# AIRDCR.net
KiCad netlist of a schematic drawn in EAGLE
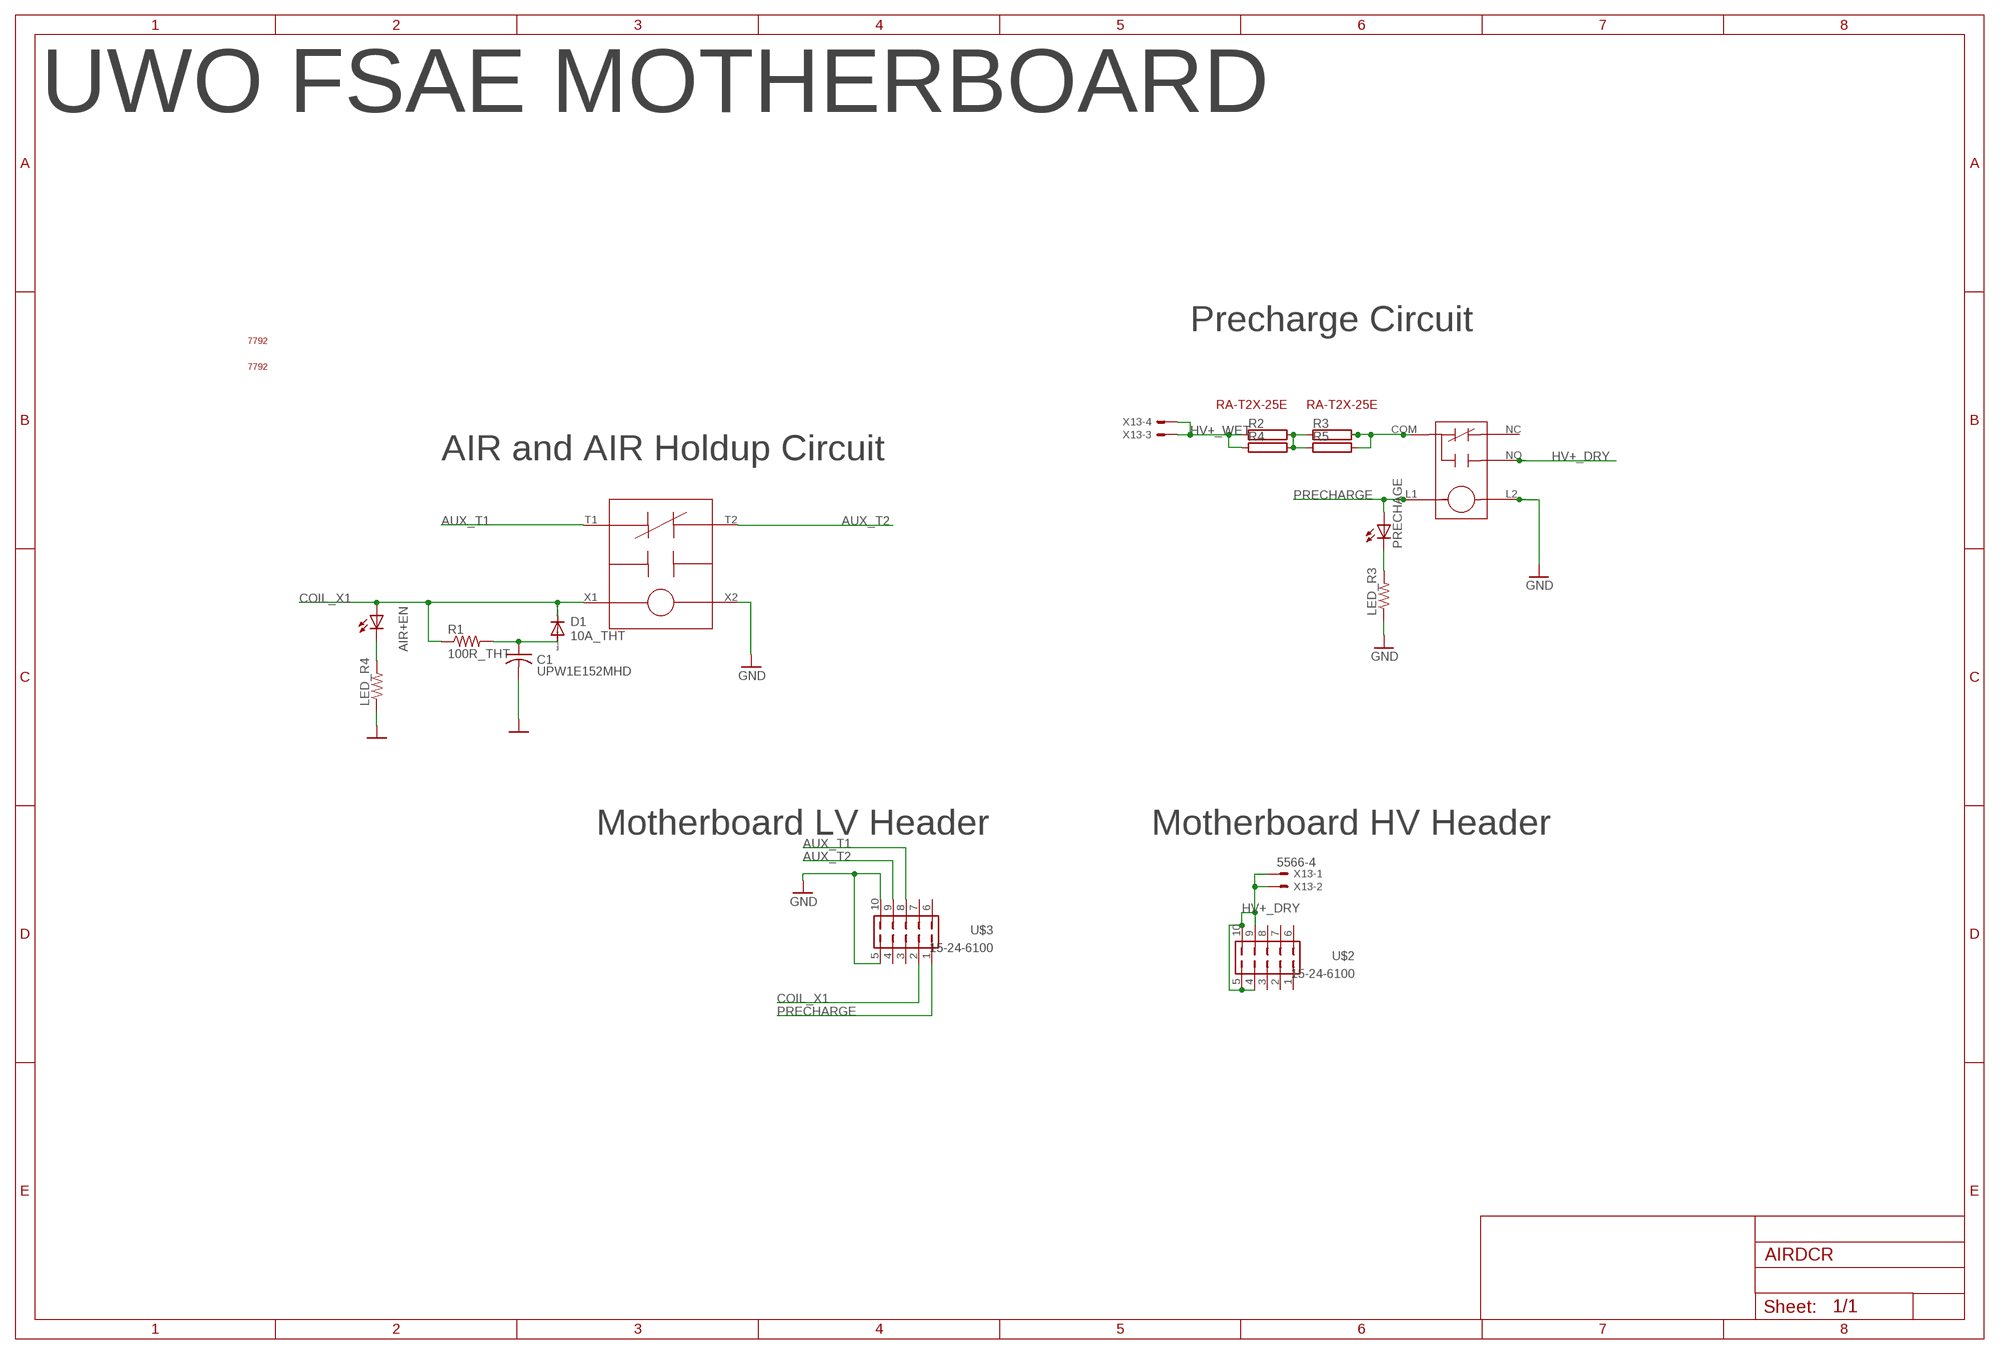
[diagram p0: schematic, sheet 1]

(export (version "E")
  (design (tool "Eeschema 10.0.6"))
  (components
    (comp (ref "AIR+EN")
      (value "LEDCHIPLED_0805")
      (footprint "eagle-import:CHIPLED_0805")
      (libsource (lib "eagle-import") (part "LEDCHIPLED_0805"))
    )
    (comp (ref "C1")
      (value "UPW1E152MHD")
      (footprint "eagle-import:CAPPRD750W65D1800H3700B")
      (libsource (lib "eagle-import") (part "AIR_HOLDUP_CAP"))
    )
    (comp (ref "D1")
      (value "10A_THT")
      (footprint "eagle-import:DIOAD1570W120L850D500B")
      (libsource (lib "eagle-import") (part "AIR_HOLDUP_DIODE"))
    )
    (comp (ref "LED_R3")
      (value "R-US_R0805")
      (footprint "eagle-import:R0805")
      (libsource (lib "eagle-import") (part "R-US_R0805"))
    )
    (comp (ref "LED_R4")
      (value "R-US_R0805")
      (footprint "eagle-import:R0805")
      (libsource (lib "eagle-import") (part "R-US_R0805"))
    )
    (comp (ref "PRECHAGE")
      (value "LEDCHIPLED_0805")
      (footprint "eagle-import:CHIPLED_0805")
      (libsource (lib "eagle-import") (part "LEDCHIPLED_0805"))
    )
    (comp (ref "R1")
      (value "100R_THT")
      (footprint "eagle-import:RESAD976W63L650D250B")
      (libsource (lib "eagle-import") (part "AIR_HOLDUP_RESISTOR"))
    )
    (comp (ref "R2")
      (value "RMG100-V")
      (footprint "eagle-import:TO-247-2V")
      (libsource (lib "eagle-import") (part "RMG100-V"))
    )
    (comp (ref "R3")
      (value "RMG100-V")
      (footprint "eagle-import:TO-247-2V")
      (libsource (lib "eagle-import") (part "RMG100-V"))
    )
    (comp (ref "R4")
      (value "RMG100-V")
      (footprint "eagle-import:TO-247-2V")
      (libsource (lib "eagle-import") (part "RMG100-V"))
    )
    (comp (ref "R5")
      (value "RMG100-V")
      (footprint "eagle-import:TO-247-2V")
      (libsource (lib "eagle-import") (part "RMG100-V"))
    )
    (comp (ref "U$1")
      (value "GV245BPB")
      (footprint "eagle-import:GV224")
      (libsource (lib "eagle-import") (part "GV224"))
    )
    (comp (ref "U$2")
      (value "15-24-6100")
      (footprint "eagle-import:15-24-6100")
      (libsource (lib "eagle-import") (part "15-24-6100"))
    )
    (comp (ref "U$3")
      (value "15-24-6100")
      (footprint "eagle-import:15-24-6100")
      (libsource (lib "eagle-import") (part "15-24-6100"))
    )
    (comp (ref "U$4")
      (value "G81C335")
      (footprint "eagle-import:G81C335")
      (libsource (lib "eagle-import") (part "G81C335"))
    )
    (comp (ref "U$5")
      (value "7792")
      (footprint "eagle-import:7792")
      (libsource (lib "eagle-import") (part "7792"))
    )
    (comp (ref "U$6")
      (value "7792")
      (footprint "eagle-import:7792")
      (libsource (lib "eagle-import") (part "7792"))
    )
    (comp (ref "U$8")
      (value "RA-T2X-25E")
      (footprint "eagle-import:RA-T2X-25E")
      (libsource (lib "eagle-import") (part "RA-T2X-25E"))
    )
    (comp (ref "U$9")
      (value "RA-T2X-25E")
      (footprint "eagle-import:RA-T2X-25E")
      (libsource (lib "eagle-import") (part "RA-T2X-25E"))
    )
    (comp (ref "X13")
      (value "5566-4")
      (footprint "eagle-import:5566-4")
      (fields (field (name "MF") "MOLEX"))
      (libsource (lib "eagle-import") (part "5566-4"))
    )
  )
  (nets
    (net (code "1") (name "/AUX_T1") (class "Default")
      (node (ref "U$1") (pin "T1") (pinfunction "T1_T1") (pintype "bidirectional"))
      (node (ref "U$3") (pin "8") (pinfunction "8_8") (pintype "passive"))
    )
    (net (code "2") (name "/AUX_T2") (class "Default")
      (node (ref "U$1") (pin "T2") (pinfunction "T2_T2") (pintype "bidirectional"))
      (node (ref "U$3") (pin "9") (pinfunction "9_9") (pintype "passive"))
    )
    (net (code "3") (name "/COIL_X1") (class "Default")
      (node (ref "AIR+EN") (pin "A") (pinfunction "A_A") (pintype "passive"))
      (node (ref "D1") (pin "1") (pinfunction "C_1") (pintype "passive"))
      (node (ref "R1") (pin "1") (pinfunction "1_1") (pintype "passive"))
      (node (ref "U$1") (pin "X1") (pinfunction "X1_X1") (pintype "bidirectional"))
      (node (ref "U$3") (pin "2") (pinfunction "2_2") (pintype "passive"))
    )
    (net (code "4") (name "/HV+_DRY") (class "Default")
      (node (ref "U$2") (pin "10") (pinfunction "10_10") (pintype "passive"))
      (node (ref "U$2") (pin "4") (pinfunction "4_4") (pintype "passive"))
      (node (ref "U$2") (pin "5") (pinfunction "5_5") (pintype "passive"))
      (node (ref "U$2") (pin "9") (pinfunction "9_9") (pintype "passive"))
      (node (ref "U$4") (pin "NO") (pinfunction "NO_NO") (pintype "bidirectional"))
      (node (ref "X13") (pin "1") (pinfunction "S_1") (pintype "passive"))
      (node (ref "X13") (pin "2") (pinfunction "S_2") (pintype "passive"))
    )
    (net (code "5") (name "/HV+_WET") (class "Default")
      (node (ref "R2") (pin "1") (pinfunction "1_1") (pintype "passive"))
      (node (ref "R4") (pin "1") (pinfunction "1_1") (pintype "passive"))
      (node (ref "X13") (pin "3") (pinfunction "S_3") (pintype "passive"))
      (node (ref "X13") (pin "4") (pinfunction "S_4") (pintype "passive"))
    )
    (net (code "6") (name "/PRECHARGE") (class "Default")
      (node (ref "PRECHAGE") (pin "A") (pinfunction "A_A") (pintype "passive"))
      (node (ref "U$3") (pin "1") (pinfunction "1_1") (pintype "passive"))
      (node (ref "U$4") (pin "L1") (pinfunction "L1_L1") (pintype "bidirectional"))
    )
    (net (code "7") (name "GND") (class "Default")
      (node (ref "C1") (pin "2") (pinfunction "2_2") (pintype "passive"))
      (node (ref "LED_R3") (pin "1") (pinfunction "1_1") (pintype "passive"))
      (node (ref "LED_R4") (pin "1") (pinfunction "1_1") (pintype "passive"))
      (node (ref "U$1") (pin "X2") (pinfunction "X2_X2") (pintype "bidirectional"))
      (node (ref "U$3") (pin "10") (pinfunction "10_10") (pintype "passive"))
      (node (ref "U$3") (pin "5") (pinfunction "5_5") (pintype "passive"))
      (node (ref "U$4") (pin "L2") (pinfunction "L2_L2") (pintype "bidirectional"))
    )
    (net (code "8") (name "Net-(AIR+EN-PadC)") (class "Default")
      (node (ref "AIR+EN") (pin "C") (pinfunction "C_C") (pintype "passive"))
      (node (ref "LED_R4") (pin "2") (pinfunction "2_2") (pintype "passive"))
    )
    (net (code "9") (name "Net-(D1-A)") (class "Default")
      (node (ref "C1") (pin "1") (pinfunction "1_1") (pintype "passive"))
      (node (ref "D1") (pin "2") (pinfunction "A_2") (pintype "passive"))
      (node (ref "R1") (pin "2") (pinfunction "2_2") (pintype "passive"))
    )
    (net (code "10") (name "Net-(LED_R3-Pad2)") (class "Default")
      (node (ref "LED_R3") (pin "2") (pinfunction "2_2") (pintype "passive"))
      (node (ref "PRECHAGE") (pin "C") (pinfunction "C_C") (pintype "passive"))
    )
    (net (code "11") (name "Net-(R2-Pad2)") (class "Default")
      (node (ref "R2") (pin "2") (pinfunction "2_2") (pintype "passive"))
      (node (ref "R3") (pin "1") (pinfunction "1_1") (pintype "passive"))
      (node (ref "R4") (pin "2") (pinfunction "2_2") (pintype "passive"))
      (node (ref "R5") (pin "1") (pinfunction "1_1") (pintype "passive"))
    )
    (net (code "12") (name "Net-(R3-Pad2)") (class "Default")
      (node (ref "R3") (pin "2") (pinfunction "2_2") (pintype "passive"))
      (node (ref "R5") (pin "2") (pinfunction "2_2") (pintype "passive"))
      (node (ref "U$4") (pin "COM") (pinfunction "COM_COM") (pintype "bidirectional"))
    )
    (net (code "13") (name "unconnected-(U$2-Pad1)") (class "Default")
      (node (ref "U$2") (pin "1") (pinfunction "1_1") (pintype "passive"))
    )
    (net (code "14") (name "unconnected-(U$2-Pad2)") (class "Default")
      (node (ref "U$2") (pin "2") (pinfunction "2_2") (pintype "passive"))
    )
    (net (code "15") (name "unconnected-(U$2-Pad3)") (class "Default")
      (node (ref "U$2") (pin "3") (pinfunction "3_3") (pintype "passive"))
    )
    (net (code "16") (name "unconnected-(U$2-Pad6)") (class "Default")
      (node (ref "U$2") (pin "6") (pinfunction "6_6") (pintype "passive"))
    )
    (net (code "17") (name "unconnected-(U$2-Pad7)") (class "Default")
      (node (ref "U$2") (pin "7") (pinfunction "7_7") (pintype "passive"))
    )
    (net (code "18") (name "unconnected-(U$2-Pad8)") (class "Default")
      (node (ref "U$2") (pin "8") (pinfunction "8_8") (pintype "passive"))
    )
    (net (code "19") (name "unconnected-(U$3-Pad3)") (class "Default")
      (node (ref "U$3") (pin "3") (pinfunction "3_3") (pintype "passive"))
    )
    (net (code "20") (name "unconnected-(U$3-Pad4)") (class "Default")
      (node (ref "U$3") (pin "4") (pinfunction "4_4") (pintype "passive"))
    )
    (net (code "21") (name "unconnected-(U$3-Pad6)") (class "Default")
      (node (ref "U$3") (pin "6") (pinfunction "6_6") (pintype "passive"))
    )
    (net (code "22") (name "unconnected-(U$3-Pad7)") (class "Default")
      (node (ref "U$3") (pin "7") (pinfunction "7_7") (pintype "passive"))
    )
    (net (code "23") (name "unconnected-(U$4-PadNC)") (class "Default")
      (node (ref "U$4") (pin "NC") (pinfunction "NC_NC") (pintype "bidirectional"))
    )
  )
)
